# Qwiic_MultiStar.net
KiCad netlist of a schematic drawn in EAGLE
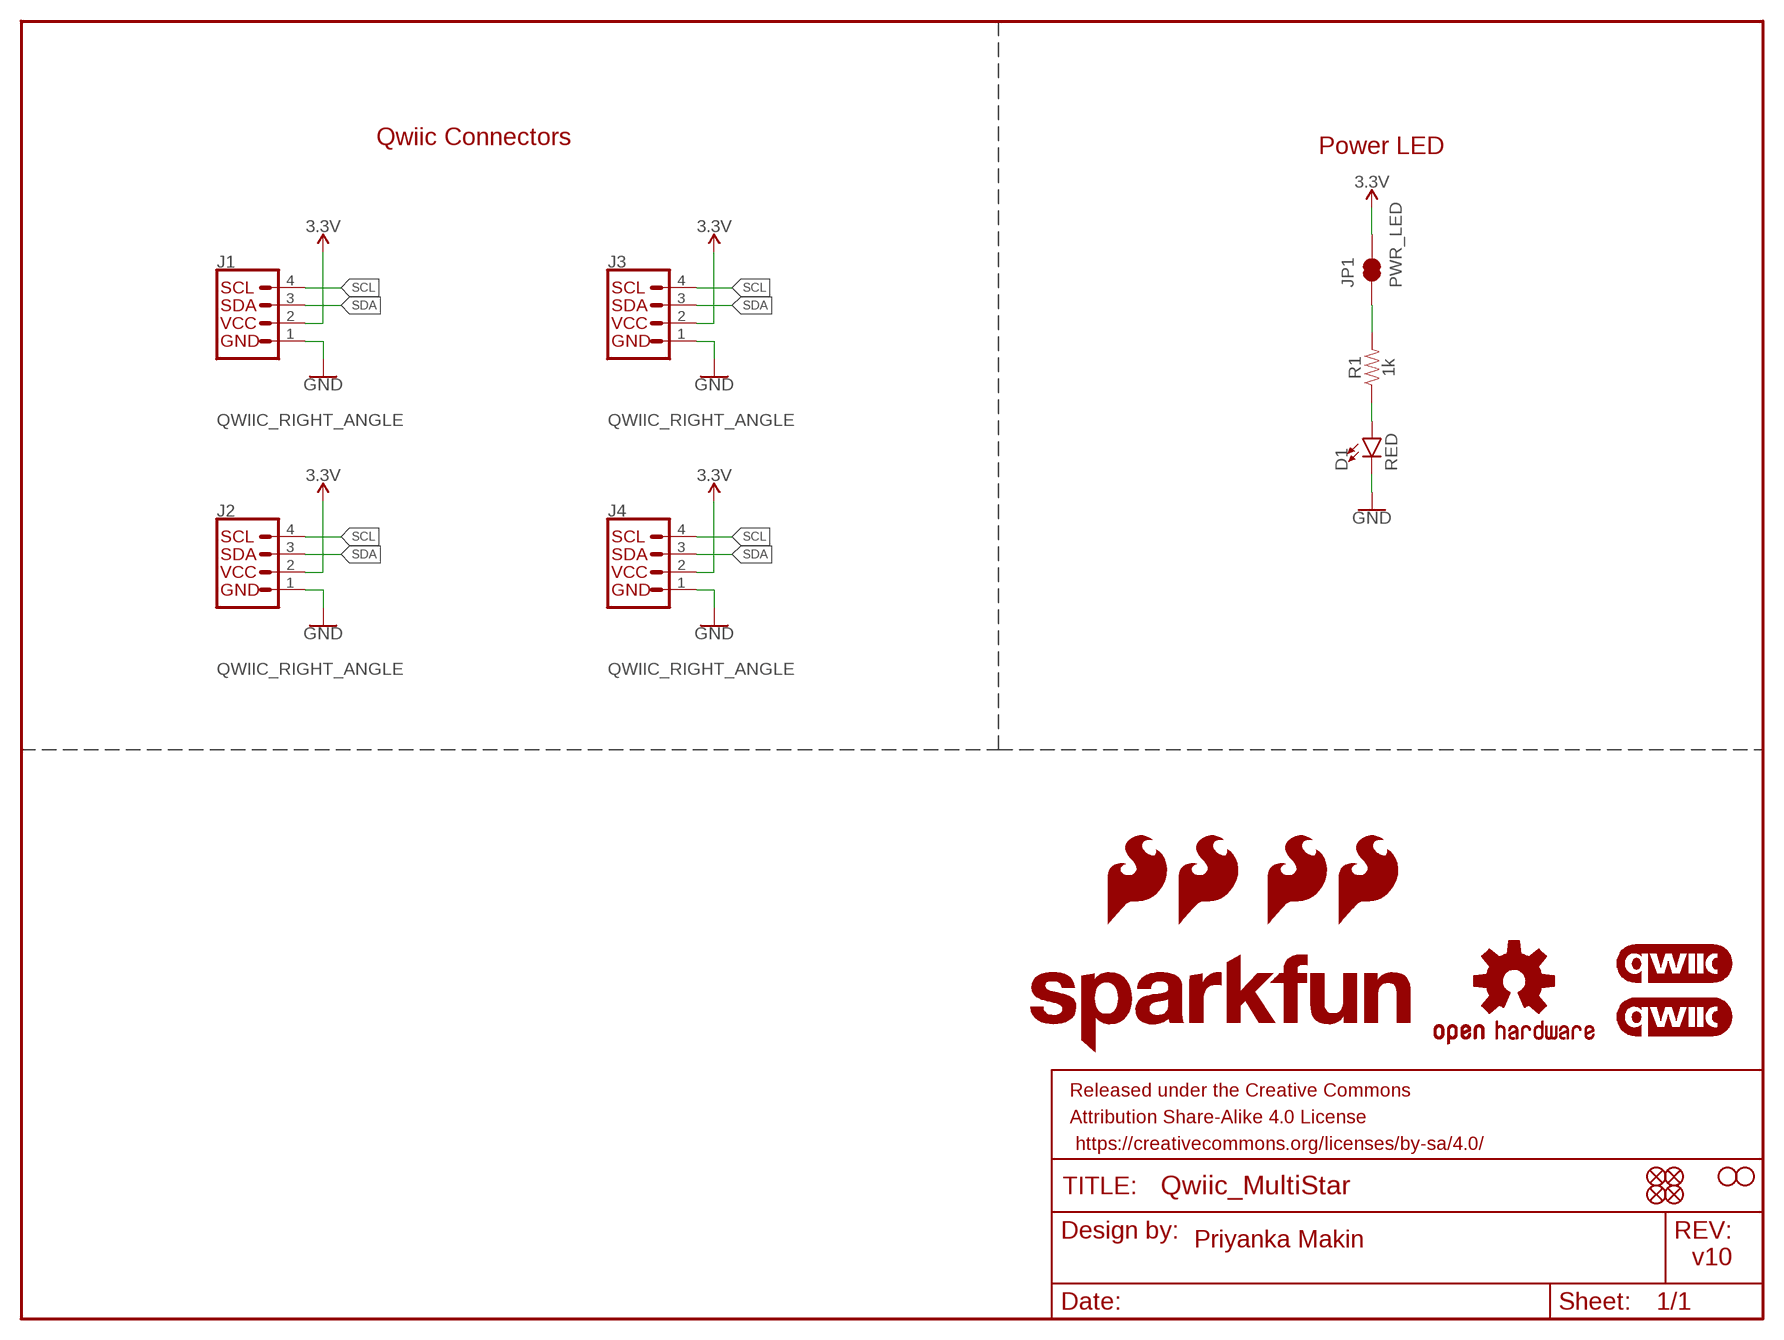
[diagram p0: schematic, sheet 1]

(export (version "E")
  (design (tool "Eeschema 10.0.6"))
  (components
    (comp (ref "D1")
      (value "RED")
      (footprint "eagle-import:LED-0603")
      (libsource (lib "eagle-import") (part "LED-RED0603"))
    )
    (comp (ref "FD1")
      (value "FIDUCIAL1X2")
      (footprint "eagle-import:FIDUCIAL-1X2")
      (libsource (lib "eagle-import") (part "FIDUCIAL1X2"))
    )
    (comp (ref "FD2")
      (value "FIDUCIAL1X2")
      (footprint "eagle-import:FIDUCIAL-1X2")
      (libsource (lib "eagle-import") (part "FIDUCIAL1X2"))
    )
    (comp (ref "FD3")
      (value "FIDUCIAL1X2")
      (footprint "eagle-import:FIDUCIAL-1X2")
      (libsource (lib "eagle-import") (part "FIDUCIAL1X2"))
    )
    (comp (ref "FD4")
      (value "FIDUCIAL1X2")
      (footprint "eagle-import:FIDUCIAL-1X2")
      (libsource (lib "eagle-import") (part "FIDUCIAL1X2"))
    )
    (comp (ref "FRAME1")
      (value "FRAME-LETTER")
      (footprint "eagle-import:CREATIVE_COMMONS")
      (libsource (lib "eagle-import") (part "FRAME-LETTER"))
    )
    (comp (ref "H1")
      (value "STAND-OFFTIGHT")
      (footprint "eagle-import:STAND-OFF-TIGHT")
      (libsource (lib "eagle-import") (part "STAND-OFFTIGHT"))
    )
    (comp (ref "H2")
      (value "STAND-OFFTIGHT")
      (footprint "eagle-import:STAND-OFF-TIGHT")
      (libsource (lib "eagle-import") (part "STAND-OFFTIGHT"))
    )
    (comp (ref "J1")
      (value "QWIIC_RIGHT_ANGLE")
      (footprint "eagle-import:JST04_1MM_RA")
      (libsource (lib "eagle-import") (part "QWIIC_CONNECTORJS-1MM"))
    )
    (comp (ref "J2")
      (value "QWIIC_RIGHT_ANGLE")
      (footprint "eagle-import:JST04_1MM_RA")
      (libsource (lib "eagle-import") (part "QWIIC_CONNECTORJS-1MM"))
    )
    (comp (ref "J3")
      (value "QWIIC_RIGHT_ANGLE")
      (footprint "eagle-import:JST04_1MM_RA")
      (libsource (lib "eagle-import") (part "QWIIC_CONNECTORJS-1MM"))
    )
    (comp (ref "J4")
      (value "QWIIC_RIGHT_ANGLE")
      (footprint "eagle-import:JST04_1MM_RA")
      (libsource (lib "eagle-import") (part "QWIIC_CONNECTORJS-1MM"))
    )
    (comp (ref "JP1")
      (value "PWR_LED")
      (footprint "eagle-import:SMT-JUMPER_2_NC_TRACE_SILK")
      (libsource (lib "eagle-import") (part "JUMPER-SMT_2_NC_TRACE_SILK"))
    )
    (comp (ref "LOGO1")
      (value "QWIIC_LOGO_5MM")
      (footprint "eagle-import:QWIIC_5MM")
      (libsource (lib "eagle-import") (part "QWIIC_LOGO_5MM"))
    )
    (comp (ref "LOGO2")
      (value "QWIIC_LOGO_5MM")
      (footprint "eagle-import:QWIIC_5MM")
      (libsource (lib "eagle-import") (part "QWIIC_LOGO_5MM"))
    )
    (comp (ref "LOGO3")
      (value "OSHW-LOGOS")
      (footprint "eagle-import:OSHW-LOGO-S")
      (libsource (lib "eagle-import") (part "OSHW-LOGOS"))
    )
    (comp (ref "LOGO4")
      (value "SFE_LOGO_NAME.2_INCH")
      (footprint "eagle-import:SFE_LOGO_NAME_.2")
      (libsource (lib "eagle-import") (part "SFE_LOGO_NAME.2_INCH"))
    )
    (comp (ref "LOGO5")
      (value "SFE_LOGO_FLAME.1_INCH")
      (footprint "eagle-import:SFE_LOGO_FLAME_.1")
      (libsource (lib "eagle-import") (part "SFE_LOGO_FLAME.1_INCH"))
    )
    (comp (ref "LOGO6")
      (value "SFE_LOGO_FLAME.1_INCH")
      (footprint "eagle-import:SFE_LOGO_FLAME_.1")
      (libsource (lib "eagle-import") (part "SFE_LOGO_FLAME.1_INCH"))
    )
    (comp (ref "LOGO7")
      (value "SFE_LOGO_FLAME.1_INCH")
      (footprint "eagle-import:SFE_LOGO_FLAME_.1")
      (libsource (lib "eagle-import") (part "SFE_LOGO_FLAME.1_INCH"))
    )
    (comp (ref "LOGO8")
      (value "SFE_LOGO_FLAME.1_INCH")
      (footprint "eagle-import:SFE_LOGO_FLAME_.1")
      (libsource (lib "eagle-import") (part "SFE_LOGO_FLAME.1_INCH"))
    )
    (comp (ref "R1")
      (value "1k")
      (footprint "eagle-import:0603")
      (libsource (lib "eagle-import") (part "1KOHM-0603-1/10W-1%"))
    )
  )
  (nets
    (net (code "1") (name "3.3V") (class "Default")
      (node (ref "J1") (pin "2") (pinfunction "2_2") (pintype "power_in"))
      (node (ref "J2") (pin "2") (pinfunction "2_2") (pintype "power_in"))
      (node (ref "J3") (pin "2") (pinfunction "2_2") (pintype "power_in"))
      (node (ref "J4") (pin "2") (pinfunction "2_2") (pintype "power_in"))
      (node (ref "JP1") (pin "2") (pinfunction "2_2") (pintype "passive"))
    )
    (net (code "2") (name "GND") (class "Default")
      (node (ref "D1") (pin "C") (pinfunction "C_C") (pintype "passive"))
      (node (ref "J1") (pin "1") (pinfunction "1_1") (pintype "power_in"))
      (node (ref "J2") (pin "1") (pinfunction "1_1") (pintype "power_in"))
      (node (ref "J3") (pin "1") (pinfunction "1_1") (pintype "power_in"))
      (node (ref "J4") (pin "1") (pinfunction "1_1") (pintype "power_in"))
    )
    (net (code "3") (name "Net-(D1-PadA)") (class "Default")
      (node (ref "D1") (pin "A") (pinfunction "A_A") (pintype "passive"))
      (node (ref "R1") (pin "1") (pinfunction "1_1") (pintype "passive"))
    )
    (net (code "4") (name "Net-(JP1-Pad1)") (class "Default")
      (node (ref "JP1") (pin "1") (pinfunction "1_1") (pintype "passive"))
      (node (ref "R1") (pin "2") (pinfunction "2_2") (pintype "passive"))
    )
    (net (code "5") (name "SCL") (class "Default")
      (node (ref "J1") (pin "4") (pinfunction "4_4") (pintype "passive"))
      (node (ref "J2") (pin "4") (pinfunction "4_4") (pintype "passive"))
      (node (ref "J3") (pin "4") (pinfunction "4_4") (pintype "passive"))
      (node (ref "J4") (pin "4") (pinfunction "4_4") (pintype "passive"))
    )
    (net (code "6") (name "SDA") (class "Default")
      (node (ref "J1") (pin "3") (pinfunction "3_3") (pintype "passive"))
      (node (ref "J2") (pin "3") (pinfunction "3_3") (pintype "passive"))
      (node (ref "J3") (pin "3") (pinfunction "3_3") (pintype "passive"))
      (node (ref "J4") (pin "3") (pinfunction "3_3") (pintype "passive"))
    )
  )
)
